# emonTx4-PiPico.net
KiCad netlist of a schematic drawn in EAGLE
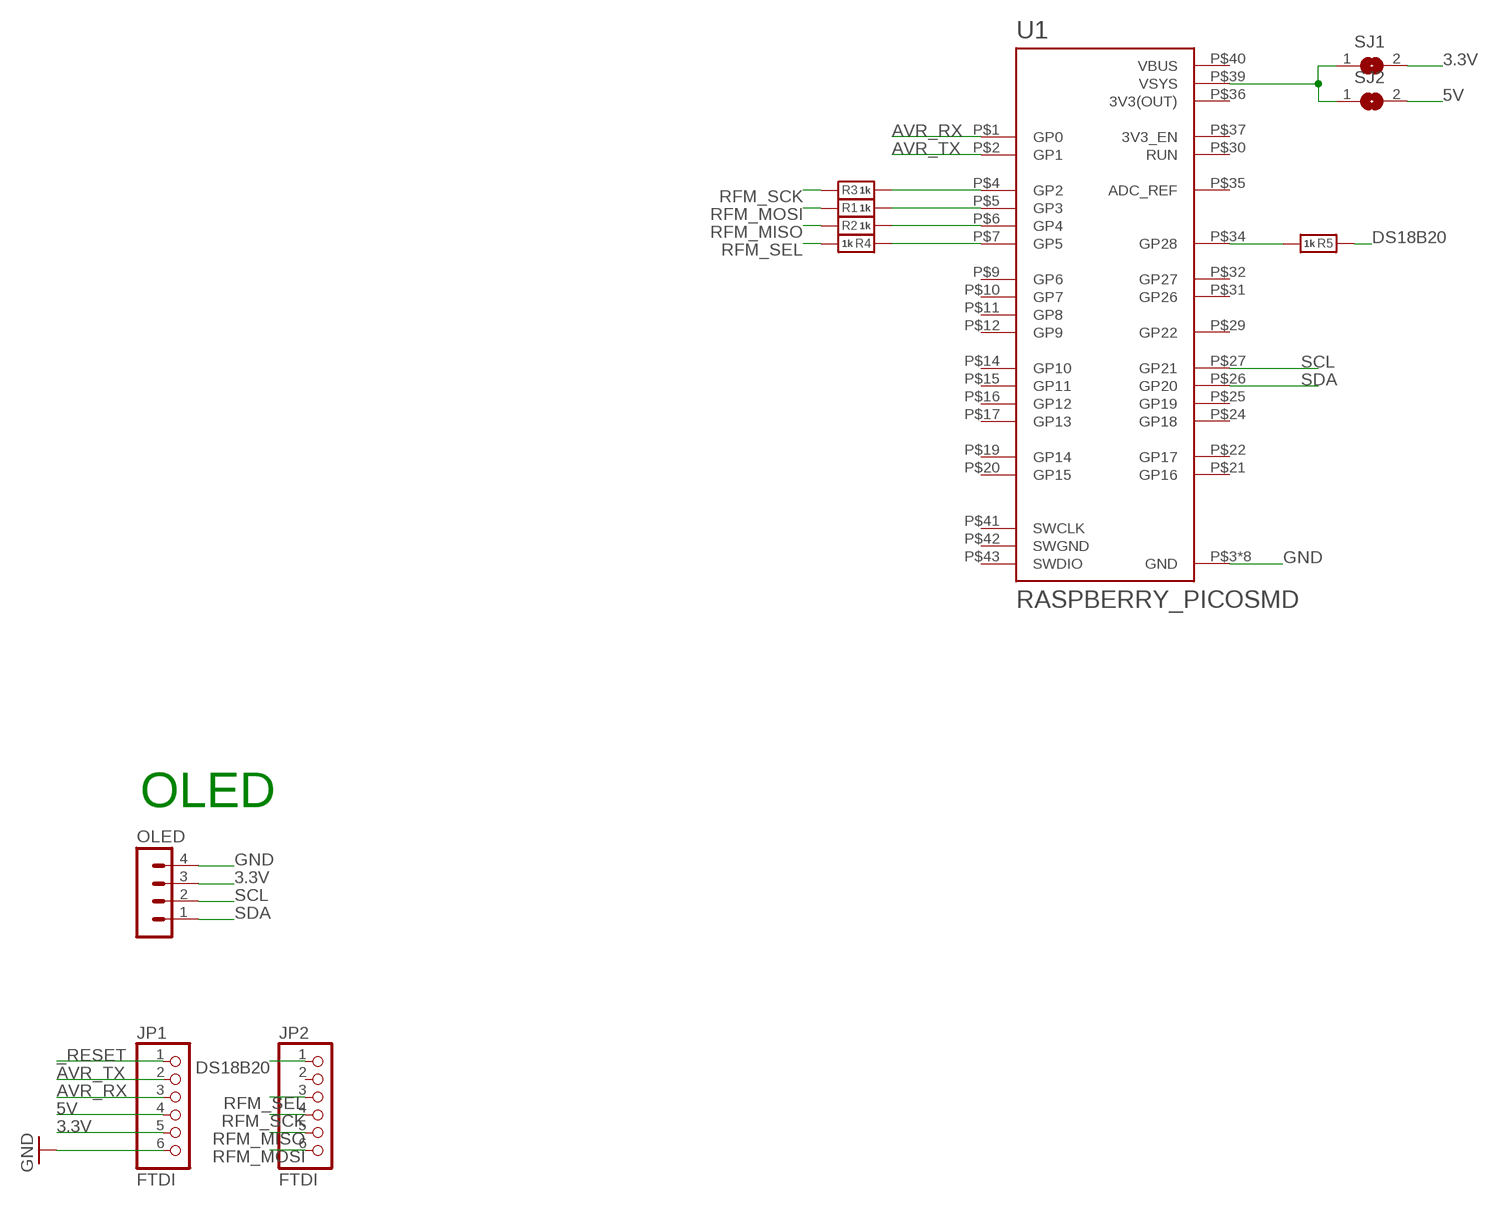
[diagram p0: schematic, sheet 1]

(export (version "E")
  (design (tool "Eeschema 10.0.6"))
  (components
    (comp (ref "JP1")
      (value "FTDI")
      (footprint "eagle-import:1X06_ROUND_70")
      (libsource (lib "eagle-import") (part "HEADER-1X670MIL"))
    )
    (comp (ref "JP2")
      (value "FTDI")
      (footprint "eagle-import:1X06_ROUND_70")
      (libsource (lib "eagle-import") (part "HEADER-1X670MIL"))
    )
    (comp (ref "OLED")
      (value "MA04-1-OLEDOLED")
      (footprint "eagle-import:MA04-1-OLED")
      (libsource (lib "eagle-import") (part "MA04-1-OLEDOLED"))
    )
    (comp (ref "R1")
      (value "1k")
      (footprint "eagle-import:_0603")
      (libsource (lib "eagle-import") (part "RESISTOR_0603"))
    )
    (comp (ref "R2")
      (value "1k")
      (footprint "eagle-import:_0603")
      (libsource (lib "eagle-import") (part "RESISTOR_0603"))
    )
    (comp (ref "R3")
      (value "1k")
      (footprint "eagle-import:_0603")
      (libsource (lib "eagle-import") (part "RESISTOR_0603"))
    )
    (comp (ref "R4")
      (value "1k")
      (footprint "eagle-import:_0603")
      (libsource (lib "eagle-import") (part "RESISTOR_0603"))
    )
    (comp (ref "R5")
      (value "1k")
      (footprint "eagle-import:_0603")
      (libsource (lib "eagle-import") (part "RESISTOR_0603"))
    )
    (comp (ref "SJ1") (value "SJ") (footprint "eagle-import:SJ") (libsource (lib "eagle-import") (part "SJ")))
    (comp (ref "SJ2") (value "SJ") (footprint "eagle-import:SJ") (libsource (lib "eagle-import") (part "SJ")))
    (comp (ref "U1")
      (value "RASPBERRY_PICOSMD")
      (footprint "eagle-import:PICO-PKG-SMD")
      (libsource (lib "eagle-import") (part "RASPBERRY_PICOSMD"))
    )
  )
  (nets
    (net (code "1") (name "/3.3V") (class "Default")
      (node (ref "JP1") (pin "5") (pinfunction "5_5") (pintype "passive"))
      (node (ref "OLED") (pin "3") (pinfunction "3_3") (pintype "passive"))
      (node (ref "SJ1") (pin "2") (pinfunction "2_2") (pintype "passive"))
    )
    (net (code "2") (name "/3V3(OUT)") (class "Default")
      (node (ref "U1") (pin "P$36") (pinfunction "3V3(OUT)_P$36") (pintype "power_in"))
    )
    (net (code "3") (name "/5V") (class "Default")
      (node (ref "JP1") (pin "4") (pinfunction "4_4") (pintype "passive"))
      (node (ref "SJ2") (pin "2") (pinfunction "2_2") (pintype "passive"))
    )
    (net (code "4") (name "/AVR_RX") (class "Default")
      (node (ref "JP1") (pin "3") (pinfunction "3_3") (pintype "passive"))
      (node (ref "U1") (pin "P$1") (pinfunction "GP0_P$1") (pintype "bidirectional"))
    )
    (net (code "5") (name "/AVR_TX") (class "Default")
      (node (ref "JP1") (pin "2") (pinfunction "2_2") (pintype "passive"))
      (node (ref "U1") (pin "P$2") (pinfunction "GP1_P$2") (pintype "bidirectional"))
    )
    (net (code "6") (name "/DS18B20") (class "Default")
      (node (ref "JP2") (pin "1") (pinfunction "1_1") (pintype "passive"))
      (node (ref "R5") (pin "2") (pinfunction "2_2") (pintype "passive"))
    )
    (net (code "7") (name "/RFM_MISO") (class "Default")
      (node (ref "JP2") (pin "5") (pinfunction "5_5") (pintype "passive"))
      (node (ref "R2") (pin "2") (pinfunction "2_2") (pintype "passive"))
    )
    (net (code "8") (name "/RFM_MOSI") (class "Default")
      (node (ref "JP2") (pin "6") (pinfunction "6_6") (pintype "passive"))
      (node (ref "R1") (pin "2") (pinfunction "2_2") (pintype "passive"))
    )
    (net (code "9") (name "/RFM_SCK") (class "Default")
      (node (ref "JP2") (pin "4") (pinfunction "4_4") (pintype "passive"))
      (node (ref "R3") (pin "2") (pinfunction "2_2") (pintype "passive"))
    )
    (net (code "10") (name "/RFM_SEL") (class "Default")
      (node (ref "JP2") (pin "3") (pinfunction "3_3") (pintype "passive"))
      (node (ref "R4") (pin "1") (pinfunction "1_1") (pintype "passive"))
    )
    (net (code "11") (name "/SCL") (class "Default")
      (node (ref "OLED") (pin "2") (pinfunction "2_2") (pintype "passive"))
      (node (ref "U1") (pin "P$27") (pinfunction "GP21_P$27") (pintype "bidirectional"))
    )
    (net (code "12") (name "/SDA") (class "Default")
      (node (ref "OLED") (pin "1") (pinfunction "1_1") (pintype "passive"))
      (node (ref "U1") (pin "P$26") (pinfunction "GP20_P$26") (pintype "bidirectional"))
    )
    (net (code "13") (name "/SWGND") (class "Default")
      (node (ref "U1") (pin "P$42") (pinfunction "SWGND_P$42") (pintype "power_in"))
    )
    (net (code "14") (name "/VBUS") (class "Default")
      (node (ref "U1") (pin "P$40") (pinfunction "VBUS_P$40") (pintype "power_in"))
    )
    (net (code "15") (name "/_RESET") (class "Default")
      (node (ref "JP1") (pin "1") (pinfunction "1_1") (pintype "passive"))
    )
    (net (code "16") (name "GND") (class "Default")
      (node (ref "JP1") (pin "6") (pinfunction "6_6") (pintype "passive"))
      (node (ref "OLED") (pin "4") (pinfunction "4_4") (pintype "passive"))
      (node (ref "U1") (pin "P$13") (pinfunction "GND_P$13") (pintype "power_in"))
      (node (ref "U1") (pin "P$18") (pinfunction "GND_P$18") (pintype "power_in"))
      (node (ref "U1") (pin "P$23") (pinfunction "GND_P$23") (pintype "power_in"))
      (node (ref "U1") (pin "P$28") (pinfunction "GND_P$28") (pintype "power_in"))
      (node (ref "U1") (pin "P$3") (pinfunction "GND_P$3") (pintype "power_in"))
      (node (ref "U1") (pin "P$33") (pinfunction "GND_P$33") (pintype "power_in"))
      (node (ref "U1") (pin "P$38") (pinfunction "GND_P$38") (pintype "power_in"))
      (node (ref "U1") (pin "P$8") (pinfunction "GND_P$8") (pintype "power_in"))
    )
    (net (code "17") (name "Net-(U1-GP2)") (class "Default")
      (node (ref "R3") (pin "1") (pinfunction "1_1") (pintype "passive"))
      (node (ref "U1") (pin "P$4") (pinfunction "GP2_P$4") (pintype "bidirectional"))
    )
    (net (code "18") (name "Net-(U1-GP3)") (class "Default")
      (node (ref "R1") (pin "1") (pinfunction "1_1") (pintype "passive"))
      (node (ref "U1") (pin "P$5") (pinfunction "GP3_P$5") (pintype "bidirectional"))
    )
    (net (code "19") (name "Net-(U1-GP4)") (class "Default")
      (node (ref "R2") (pin "1") (pinfunction "1_1") (pintype "passive"))
      (node (ref "U1") (pin "P$6") (pinfunction "GP4_P$6") (pintype "bidirectional"))
    )
    (net (code "20") (name "Net-(U1-GP5)") (class "Default")
      (node (ref "R4") (pin "2") (pinfunction "2_2") (pintype "passive"))
      (node (ref "U1") (pin "P$7") (pinfunction "GP5_P$7") (pintype "bidirectional"))
    )
    (net (code "21") (name "Net-(U1-GP28)") (class "Default")
      (node (ref "R5") (pin "1") (pinfunction "1_1") (pintype "passive"))
      (node (ref "U1") (pin "P$34") (pinfunction "GP28_P$34") (pintype "bidirectional"))
    )
    (net (code "22") (name "Net-(U1-VSYS)") (class "Default")
      (node (ref "SJ1") (pin "1") (pinfunction "1_1") (pintype "passive"))
      (node (ref "SJ2") (pin "1") (pinfunction "1_1") (pintype "passive"))
      (node (ref "U1") (pin "P$39") (pinfunction "VSYS_P$39") (pintype "power_in"))
    )
    (net (code "23") (name "unconnected-(JP2-Pad2)") (class "Default")
      (node (ref "JP2") (pin "2") (pinfunction "2_2") (pintype "passive"))
    )
    (net (code "24") (name "unconnected-(U1-3V3_EN-PadP$37)") (class "Default")
      (node (ref "U1") (pin "P$37") (pinfunction "3V3_EN_P$37") (pintype "input"))
    )
    (net (code "25") (name "unconnected-(U1-ADC_REF-PadP$35)") (class "Default")
      (node (ref "U1") (pin "P$35") (pinfunction "ADC_REF_P$35") (pintype "input"))
    )
    (net (code "26") (name "unconnected-(U1-GP6-PadP$9)") (class "Default")
      (node (ref "U1") (pin "P$9") (pinfunction "GP6_P$9") (pintype "bidirectional"))
    )
    (net (code "27") (name "unconnected-(U1-GP7-PadP$10)") (class "Default")
      (node (ref "U1") (pin "P$10") (pinfunction "GP7_P$10") (pintype "bidirectional"))
    )
    (net (code "28") (name "unconnected-(U1-GP8-PadP$11)") (class "Default")
      (node (ref "U1") (pin "P$11") (pinfunction "GP8_P$11") (pintype "bidirectional"))
    )
    (net (code "29") (name "unconnected-(U1-GP9-PadP$12)") (class "Default")
      (node (ref "U1") (pin "P$12") (pinfunction "GP9_P$12") (pintype "bidirectional"))
    )
    (net (code "30") (name "unconnected-(U1-GP10-PadP$14)") (class "Default")
      (node (ref "U1") (pin "P$14") (pinfunction "GP10_P$14") (pintype "bidirectional"))
    )
    (net (code "31") (name "unconnected-(U1-GP11-PadP$15)") (class "Default")
      (node (ref "U1") (pin "P$15") (pinfunction "GP11_P$15") (pintype "bidirectional"))
    )
    (net (code "32") (name "unconnected-(U1-GP12-PadP$16)") (class "Default")
      (node (ref "U1") (pin "P$16") (pinfunction "GP12_P$16") (pintype "bidirectional"))
    )
    (net (code "33") (name "unconnected-(U1-GP13-PadP$17)") (class "Default")
      (node (ref "U1") (pin "P$17") (pinfunction "GP13_P$17") (pintype "bidirectional"))
    )
    (net (code "34") (name "unconnected-(U1-GP14-PadP$19)") (class "Default")
      (node (ref "U1") (pin "P$19") (pinfunction "GP14_P$19") (pintype "bidirectional"))
    )
    (net (code "35") (name "unconnected-(U1-GP15-PadP$20)") (class "Default")
      (node (ref "U1") (pin "P$20") (pinfunction "GP15_P$20") (pintype "bidirectional"))
    )
    (net (code "36") (name "unconnected-(U1-GP16-PadP$21)") (class "Default")
      (node (ref "U1") (pin "P$21") (pinfunction "GP16_P$21") (pintype "bidirectional"))
    )
    (net (code "37") (name "unconnected-(U1-GP17-PadP$22)") (class "Default")
      (node (ref "U1") (pin "P$22") (pinfunction "GP17_P$22") (pintype "bidirectional"))
    )
    (net (code "38") (name "unconnected-(U1-GP18-PadP$24)") (class "Default")
      (node (ref "U1") (pin "P$24") (pinfunction "GP18_P$24") (pintype "bidirectional"))
    )
    (net (code "39") (name "unconnected-(U1-GP19-PadP$25)") (class "Default")
      (node (ref "U1") (pin "P$25") (pinfunction "GP19_P$25") (pintype "bidirectional"))
    )
    (net (code "40") (name "unconnected-(U1-GP22-PadP$29)") (class "Default")
      (node (ref "U1") (pin "P$29") (pinfunction "GP22_P$29") (pintype "bidirectional"))
    )
    (net (code "41") (name "unconnected-(U1-GP26-PadP$31)") (class "Default")
      (node (ref "U1") (pin "P$31") (pinfunction "GP26_P$31") (pintype "bidirectional"))
    )
    (net (code "42") (name "unconnected-(U1-GP27-PadP$32)") (class "Default")
      (node (ref "U1") (pin "P$32") (pinfunction "GP27_P$32") (pintype "bidirectional"))
    )
    (net (code "43") (name "unconnected-(U1-RUN-PadP$30)") (class "Default")
      (node (ref "U1") (pin "P$30") (pinfunction "RUN_P$30") (pintype "input"))
    )
    (net (code "44") (name "unconnected-(U1-SWCLK-PadP$41)") (class "Default")
      (node (ref "U1") (pin "P$41") (pinfunction "SWCLK_P$41") (pintype "input"))
    )
    (net (code "45") (name "unconnected-(U1-SWDIO-PadP$43)") (class "Default")
      (node (ref "U1") (pin "P$43") (pinfunction "SWDIO_P$43") (pintype "bidirectional"))
    )
  )
)
